# IN.net
KiCad netlist of a schematic drawn in Altium Designer
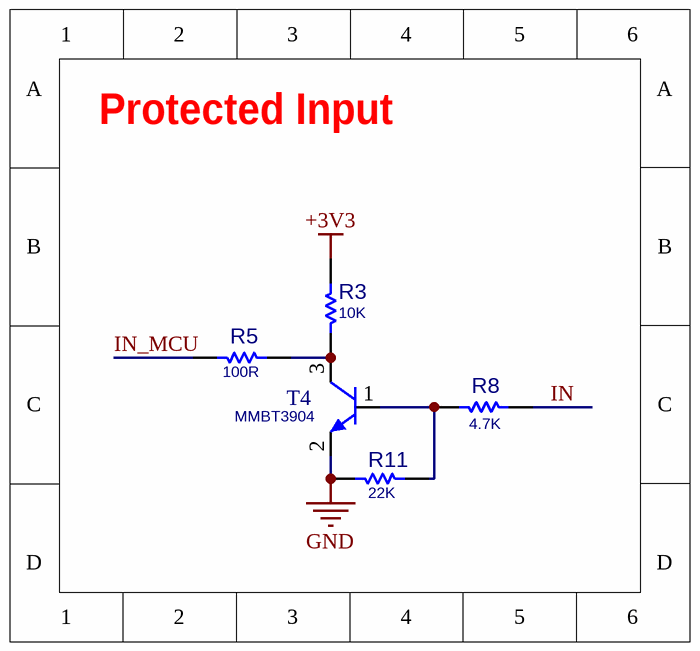
[diagram p0: IN.SchDoc]

(export (version "E")
  (design (tool "Eeschema 10.0.6"))
  (components
    (comp (ref "R3")
      (value "10K")
      (footprint "R0603")
      (description "RES, SMD")
      (fields (field (name "MANF_P#") "RK73H1ETTP4701F") (field (name "MANF") "KOA SPEER"))
      (libsource (lib "PW Components 97_481") (part "RES_SMD"))
    )
    (comp (ref "R5")
      (value "100R")
      (footprint "R0603")
      (description "RES, SMD")
      (fields (field (name "MANF_P#") "RK73H1ETTP4701F") (field (name "MANF") "KOA SPEER"))
      (libsource (lib "PW Components 97_481") (part "RES_SMD"))
    )
    (comp (ref "R8")
      (value "4.7K")
      (footprint "R0603")
      (description "RES, SMD")
      (fields (field (name "MANF_P#") "RK73H1ETTP4701F") (field (name "MANF") "KOA SPEER"))
      (libsource (lib "PW Components 97_481") (part "RES_SMD"))
    )
    (comp (ref "R11")
      (value "22K")
      (footprint "R0603")
      (description "RES, SMD")
      (fields (field (name "MANF_P#") "RK73H1ETTP4701F") (field (name "MANF") "KOA SPEER"))
      (libsource (lib "PW Components 97_481") (part "RES_SMD"))
    )
    (comp (ref "T4")
      (value "MMBT3904")
      (footprint "SOT23_3")
      (description "BJT, NPN, 40v, 0.2A, SMD, SOT23")
      (fields (field (name "MANF") "Diodes, NXP, FAIRCHILD, ON"))
      (libsource (lib "Transistor BJT") (part "NPN_MMBT3904_SOT23"))
    )
  )
  (nets
    (net (code "1") (name "+3V3") (class "Default")
      (node (ref "R3") (pin "2") (pinfunction "2_2") (pintype "passive"))
    )
    (net (code "2") (name "/IN") (class "Default")
      (node (ref "R8") (pin "2") (pinfunction "2_2") (pintype "passive"))
    )
    (net (code "3") (name "/IN_MCU") (class "Default")
      (node (ref "R5") (pin "1") (pinfunction "1_1") (pintype "passive"))
    )
    (net (code "4") (name "GND") (class "Default")
      (node (ref "R11") (pin "1") (pinfunction "1_1") (pintype "passive"))
      (node (ref "T4") (pin "2") (pinfunction "E_2") (pintype "passive"))
    )
    (net (code "5") (name "Net-(T4-B)") (class "Default")
      (node (ref "R11") (pin "2") (pinfunction "2_2") (pintype "passive"))
      (node (ref "R8") (pin "1") (pinfunction "1_1") (pintype "passive"))
      (node (ref "T4") (pin "1") (pinfunction "B_1") (pintype "passive"))
    )
    (net (code "6") (name "Net-(T4-C)") (class "Default")
      (node (ref "R3") (pin "1") (pinfunction "1_1") (pintype "passive"))
      (node (ref "R5") (pin "2") (pinfunction "2_2") (pintype "passive"))
      (node (ref "T4") (pin "3") (pinfunction "C_3") (pintype "passive"))
    )
  )
)
